# LPCB221_-_CORE_INTERFACE.net
KiCad netlist of a schematic drawn in Altium Designer
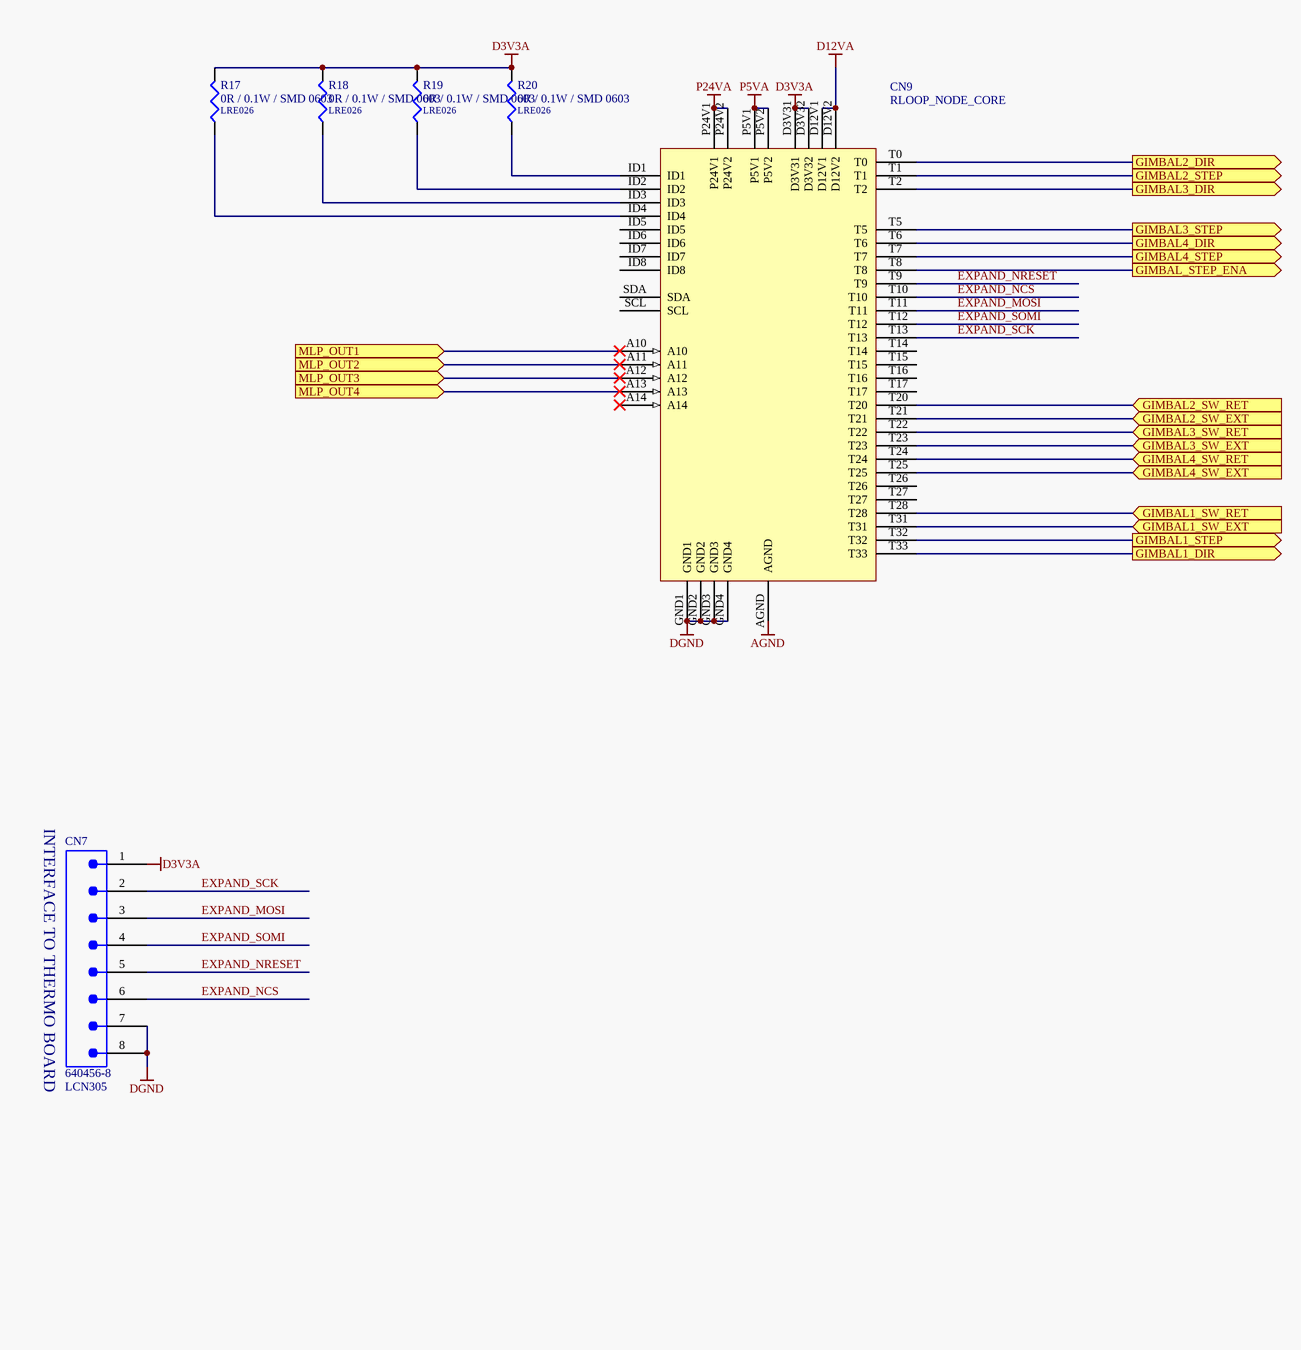
[diagram p0: LPCB221 - CORE INTERFACE.SchDoc]

(export (version "E")
  (design (tool "Eeschema 10.0.6"))
  (components
    (comp (ref "CN7")
      (value "640456-8")
      (footprint "640456-8")
      (description "Connector, Male Header, 8 Way")
      (fields (field (name "LDL_NUMBER") "LCN305"))
      (libsource (lib "LDL_Connectors") (part "640456-8"))
    )
    (comp (ref "CN9")
      (value "RLOOP_NODE_CORE")
      (footprint "RLOOP_NODE_CORE")
      (description "rLoop Node Core Connector")
      (libsource (lib "LDL_Connectors") (part "RLOOP_NODE_CORE"))
    )
    (comp (ref "R17")
      (value "0R / 0.1W / SMD 0603")
      (footprint "LFP020__CR1608-0603-IPC7351_B")
      (description "Resistor, Ceramic Chip, 0R, 0.1W, SMD 0603 [LRE026]")
      (fields (field (name "LDL_NUMBER") "LRE026"))
      (libsource (lib "LDL_Resistors") (part "0R / 0.1W / SMD 0603"))
    )
    (comp (ref "R18")
      (value "0R / 0.1W / SMD 0603")
      (footprint "LFP020__CR1608-0603-IPC7351_B")
      (description "Resistor, Ceramic Chip, 0R, 0.1W, SMD 0603 [LRE026]")
      (fields (field (name "LDL_NUMBER") "LRE026"))
      (libsource (lib "LDL_Resistors") (part "0R / 0.1W / SMD 0603"))
    )
    (comp (ref "R19")
      (value "0R / 0.1W / SMD 0603")
      (footprint "LFP020__CR1608-0603-IPC7351_B")
      (description "Resistor, Ceramic Chip, 0R, 0.1W, SMD 0603 [LRE026]")
      (fields (field (name "LDL_NUMBER") "LRE026"))
      (libsource (lib "LDL_Resistors") (part "0R / 0.1W / SMD 0603"))
    )
    (comp (ref "R20")
      (value "0R / 0.1W / SMD 0603")
      (footprint "LFP020__CR1608-0603-IPC7351_B")
      (description "Resistor, Ceramic Chip, 0R, 0.1W, SMD 0603 [LRE026]")
      (fields (field (name "LDL_NUMBER") "LRE026"))
      (libsource (lib "LDL_Resistors") (part "0R / 0.1W / SMD 0603"))
    )
  )
  (nets
    (net (code "1") (name "/EXPAND_MOSI") (class "Default")
      (node (ref "CN7") (pin "3") (pinfunction "3_3") (pintype "passive"))
      (node (ref "CN9") (pin "T11") (pinfunction "T11_T11") (pintype "passive"))
    )
    (net (code "2") (name "/EXPAND_NCS") (class "Default")
      (node (ref "CN7") (pin "6") (pinfunction "6_6") (pintype "passive"))
      (node (ref "CN9") (pin "T10") (pinfunction "T10_T10") (pintype "passive"))
    )
    (net (code "3") (name "/EXPAND_NRESET") (class "Default")
      (node (ref "CN7") (pin "5") (pinfunction "5_5") (pintype "passive"))
      (node (ref "CN9") (pin "T9") (pinfunction "T9_T9") (pintype "passive"))
    )
    (net (code "4") (name "/EXPAND_SCK") (class "Default")
      (node (ref "CN7") (pin "2") (pinfunction "2_2") (pintype "passive"))
      (node (ref "CN9") (pin "T13") (pinfunction "T13_T13") (pintype "passive"))
    )
    (net (code "5") (name "/EXPAND_SOMI") (class "Default")
      (node (ref "CN7") (pin "4") (pinfunction "4_4") (pintype "passive"))
      (node (ref "CN9") (pin "T12") (pinfunction "T12_T12") (pintype "passive"))
    )
    (net (code "6") (name "/GIMBAL1_DIR") (class "Default")
      (node (ref "CN9") (pin "T33") (pinfunction "T33_T33") (pintype "passive"))
    )
    (net (code "7") (name "/GIMBAL1_STEP") (class "Default")
      (node (ref "CN9") (pin "T32") (pinfunction "T32_T32") (pintype "passive"))
    )
    (net (code "8") (name "/GIMBAL1_SW_EXT") (class "Default")
      (node (ref "CN9") (pin "T31") (pinfunction "T31_T31") (pintype "passive"))
    )
    (net (code "9") (name "/GIMBAL1_SW_RET") (class "Default")
      (node (ref "CN9") (pin "T28") (pinfunction "T28_T28") (pintype "passive"))
    )
    (net (code "10") (name "/GIMBAL2_DIR") (class "Default")
      (node (ref "CN9") (pin "T0") (pinfunction "T0_T0") (pintype "passive"))
    )
    (net (code "11") (name "/GIMBAL2_STEP") (class "Default")
      (node (ref "CN9") (pin "T1") (pinfunction "T1_T1") (pintype "passive"))
    )
    (net (code "12") (name "/GIMBAL2_SW_EXT") (class "Default")
      (node (ref "CN9") (pin "T21") (pinfunction "T21_T21") (pintype "passive"))
    )
    (net (code "13") (name "/GIMBAL2_SW_RET") (class "Default")
      (node (ref "CN9") (pin "T20") (pinfunction "T20_T20") (pintype "passive"))
    )
    (net (code "14") (name "/GIMBAL3_DIR") (class "Default")
      (node (ref "CN9") (pin "T2") (pinfunction "T2_T2") (pintype "passive"))
    )
    (net (code "15") (name "/GIMBAL3_STEP") (class "Default")
      (node (ref "CN9") (pin "T5") (pinfunction "T5_T5") (pintype "passive"))
    )
    (net (code "16") (name "/GIMBAL3_SW_EXT") (class "Default")
      (node (ref "CN9") (pin "T23") (pinfunction "T23_T23") (pintype "passive"))
    )
    (net (code "17") (name "/GIMBAL3_SW_RET") (class "Default")
      (node (ref "CN9") (pin "T22") (pinfunction "T22_T22") (pintype "passive"))
    )
    (net (code "18") (name "/GIMBAL4_DIR") (class "Default")
      (node (ref "CN9") (pin "T6") (pinfunction "T6_T6") (pintype "passive"))
    )
    (net (code "19") (name "/GIMBAL4_STEP") (class "Default")
      (node (ref "CN9") (pin "T7") (pinfunction "T7_T7") (pintype "passive"))
    )
    (net (code "20") (name "/GIMBAL4_SW_EXT") (class "Default")
      (node (ref "CN9") (pin "T25") (pinfunction "T25_T25") (pintype "passive"))
    )
    (net (code "21") (name "/GIMBAL4_SW_RET") (class "Default")
      (node (ref "CN9") (pin "T24") (pinfunction "T24_T24") (pintype "passive"))
    )
    (net (code "22") (name "/GIMBAL_STEP_ENA") (class "Default")
      (node (ref "CN9") (pin "T8") (pinfunction "T8_T8") (pintype "passive"))
    )
    (net (code "23") (name "/MLP_OUT1") (class "Default")
      (node (ref "CN9") (pin "A10") (pinfunction "A10_A10") (pintype "input+no_connect"))
    )
    (net (code "24") (name "/MLP_OUT2") (class "Default")
      (node (ref "CN9") (pin "A11") (pinfunction "A11_A11") (pintype "input+no_connect"))
    )
    (net (code "25") (name "/MLP_OUT3") (class "Default")
      (node (ref "CN9") (pin "A12") (pinfunction "A12_A12") (pintype "input+no_connect"))
    )
    (net (code "26") (name "/MLP_OUT4") (class "Default")
      (node (ref "CN9") (pin "A13") (pinfunction "A13_A13") (pintype "input+no_connect"))
    )
    (net (code "27") (name "AGND") (class "Default")
      (node (ref "CN9") (pin "AGND") (pinfunction "AGND_AGND") (pintype "power_in"))
    )
    (net (code "28") (name "D3V3A") (class "Default")
      (node (ref "CN7") (pin "1") (pinfunction "1_1") (pintype "passive"))
      (node (ref "CN9") (pin "D3V31") (pinfunction "D3V31_D3V31") (pintype "power_in"))
      (node (ref "CN9") (pin "D3V32") (pinfunction "D3V32_D3V32") (pintype "power_in"))
      (node (ref "R17") (pin "2") (pintype "passive"))
      (node (ref "R18") (pin "2") (pintype "passive"))
      (node (ref "R19") (pin "2") (pintype "passive"))
      (node (ref "R20") (pin "2") (pintype "passive"))
    )
    (net (code "29") (name "D12VA") (class "Default")
      (node (ref "CN9") (pin "D12V1") (pinfunction "D12V1_D12V1") (pintype "power_in"))
      (node (ref "CN9") (pin "D12V2") (pinfunction "D12V2_D12V2") (pintype "power_in"))
    )
    (net (code "30") (name "DGND") (class "Default")
      (node (ref "CN7") (pin "7") (pinfunction "7_7") (pintype "passive"))
      (node (ref "CN7") (pin "8") (pinfunction "8_8") (pintype "passive"))
      (node (ref "CN9") (pin "GND1") (pinfunction "GND1_GND1") (pintype "power_in"))
      (node (ref "CN9") (pin "GND2") (pinfunction "GND2_GND2") (pintype "power_in"))
      (node (ref "CN9") (pin "GND3") (pinfunction "GND3_GND3") (pintype "power_in"))
      (node (ref "CN9") (pin "GND4") (pinfunction "GND4_GND4") (pintype "power_in"))
    )
    (net (code "31") (name "Net-(CN9-PadID1)") (class "Default")
      (node (ref "CN9") (pin "ID1") (pinfunction "ID1_ID1") (pintype "passive"))
      (node (ref "R20") (pin "1") (pintype "passive"))
    )
    (net (code "32") (name "Net-(CN9-PadID2)") (class "Default")
      (node (ref "CN9") (pin "ID2") (pinfunction "ID2_ID2") (pintype "passive"))
      (node (ref "R19") (pin "1") (pintype "passive"))
    )
    (net (code "33") (name "Net-(CN9-PadID3)") (class "Default")
      (node (ref "CN9") (pin "ID3") (pinfunction "ID3_ID3") (pintype "passive"))
      (node (ref "R18") (pin "1") (pintype "passive"))
    )
    (net (code "34") (name "Net-(CN9-PadID4)") (class "Default")
      (node (ref "CN9") (pin "ID4") (pinfunction "ID4_ID4") (pintype "passive"))
      (node (ref "R17") (pin "1") (pintype "passive"))
    )
    (net (code "35") (name "P5VA") (class "Default")
      (node (ref "CN9") (pin "P5V1") (pinfunction "P5V1_P5V1") (pintype "power_in"))
      (node (ref "CN9") (pin "P5V2") (pinfunction "P5V2_P5V2") (pintype "power_in"))
    )
    (net (code "36") (name "P24VA") (class "Default")
      (node (ref "CN9") (pin "P24V1") (pinfunction "P24V1_P24V1") (pintype "power_in"))
      (node (ref "CN9") (pin "P24V2") (pinfunction "P24V2_P24V2") (pintype "power_in"))
    )
    (net (code "37") (name "unconnected-(CN9-PadA14)") (class "Default")
      (node (ref "CN9") (pin "A14") (pinfunction "A14_A14") (pintype "input+no_connect"))
    )
    (net (code "38") (name "unconnected-(CN9-PadID5)") (class "Default")
      (node (ref "CN9") (pin "ID5") (pinfunction "ID5_ID5") (pintype "passive"))
    )
    (net (code "39") (name "unconnected-(CN9-PadID6)") (class "Default")
      (node (ref "CN9") (pin "ID6") (pinfunction "ID6_ID6") (pintype "passive"))
    )
    (net (code "40") (name "unconnected-(CN9-PadID7)") (class "Default")
      (node (ref "CN9") (pin "ID7") (pinfunction "ID7_ID7") (pintype "passive"))
    )
    (net (code "41") (name "unconnected-(CN9-PadID8)") (class "Default")
      (node (ref "CN9") (pin "ID8") (pinfunction "ID8_ID8") (pintype "passive"))
    )
    (net (code "42") (name "unconnected-(CN9-PadSCL)") (class "Default")
      (node (ref "CN9") (pin "SCL") (pinfunction "SCL_SCL") (pintype "passive"))
    )
    (net (code "43") (name "unconnected-(CN9-PadSDA)") (class "Default")
      (node (ref "CN9") (pin "SDA") (pinfunction "SDA_SDA") (pintype "passive"))
    )
    (net (code "44") (name "unconnected-(CN9-PadT14)") (class "Default")
      (node (ref "CN9") (pin "T14") (pinfunction "T14_T14") (pintype "passive"))
    )
    (net (code "45") (name "unconnected-(CN9-PadT15)") (class "Default")
      (node (ref "CN9") (pin "T15") (pinfunction "T15_T15") (pintype "passive"))
    )
    (net (code "46") (name "unconnected-(CN9-PadT16)") (class "Default")
      (node (ref "CN9") (pin "T16") (pinfunction "T16_T16") (pintype "passive"))
    )
    (net (code "47") (name "unconnected-(CN9-PadT17)") (class "Default")
      (node (ref "CN9") (pin "T17") (pinfunction "T17_T17") (pintype "passive"))
    )
    (net (code "48") (name "unconnected-(CN9-PadT26)") (class "Default")
      (node (ref "CN9") (pin "T26") (pinfunction "T26_T26") (pintype "passive"))
    )
    (net (code "49") (name "unconnected-(CN9-PadT27)") (class "Default")
      (node (ref "CN9") (pin "T27") (pinfunction "T27_T27") (pintype "passive"))
    )
  )
)
